# CamLink.net
KiCad netlist of a schematic drawn in Altium Designer
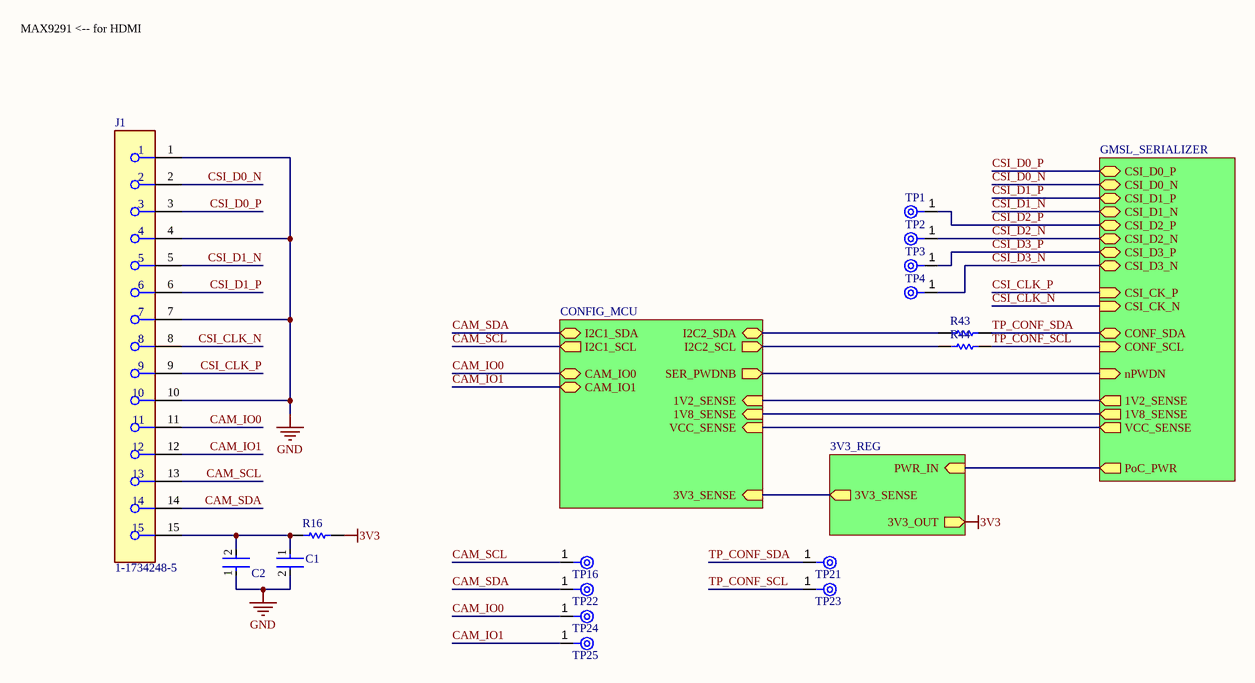
[diagram p0: CamLink.SchDoc]

(export (version "E")
  (design (tool "Eeschema 10.0.6"))
  (components
    (comp (ref "C1")
      (value "CL05A106MP5NUNC")
      (footprint "FP-CL05A106MP5NUNC-MFG")
      (description "CAP CER 10UF 10V X5R 0402")
      (fields
        (field (name "OCTOPART") "https://octopart.com/cl05a106mp5nunc-samsung-22457395")
        (field (name "TOLERANCE") "20%")
      )
      (libsource (lib "Altium Content Vault") (part "b4654b650e69147ec39a6b967a45e02"))
    )
    (comp (ref "C2")
      (value "C1005X7R1H104K050BB")
      (footprint "FP-C1005-050-0_05-IPC_C")
      (description "Multilayer Ceramic Capacitors 100nF ±10% 50V X7R SMD 0402")
      (fields (field (name "VOLTAGE") "50V") (field (name "TOLERANCE") "10%"))
      (libsource (lib "Altium Content Vault") (part "b4654b650e69147ec39a6b967a45e02"))
    )
    (comp (ref "J1")
      (value "1-1734248-5")
      (footprint "FP-1-1734248-5-MFG")
      (description "CONN FPC VERT 15POS 1.00MM SMD")
      (fields
        (field (name "MANUFACTURER") "TE")
        (field (name "OCTOPART") "https://octopart.com/1-1734248-5-te+connectivity-40620898")
      )
      (libsource (lib "Altium Content Vault") (part "a0777be16b290adccad2a8f9338c195"))
    )
    (comp (ref "R16")
      (value "RC0402JR-070RL")
      (footprint "RESC1005X40X25NL05T10")
      (fields (field (name "MANUFACTURER") "Yageo / Phycomp"))
      (libsource (lib "Altium Content Vault") (part "RES"))
    )
    (comp (ref "R43")
      (value "RC0402JR-070RL")
      (footprint "RESC1005X40X25NL05T10")
      (fields (field (name "MANUFACTURER") "Yageo / Phycomp"))
      (libsource (lib "Altium Content Vault") (part "RES"))
    )
    (comp (ref "R44")
      (value "RC0402JR-070RL")
      (footprint "RESC1005X40X25NL05T10")
      (fields (field (name "MANUFACTURER") "Yageo / Phycomp"))
      (libsource (lib "Altium Content Vault") (part "RES"))
    )
    (comp (ref "TP1")
      (value "TPAD6R")
      (footprint "New footprint 1")
      (description "Test Point .6mm")
      (libsource (lib "Space Concordia") (part "TP"))
    )
    (comp (ref "TP2")
      (value "TPAD6R")
      (footprint "New footprint 1")
      (description "Test Point .6mm")
      (libsource (lib "Space Concordia") (part "TP"))
    )
    (comp (ref "TP3")
      (value "TPAD6R")
      (footprint "New footprint 1")
      (description "Test Point .6mm")
      (libsource (lib "Space Concordia") (part "TP"))
    )
    (comp (ref "TP4")
      (value "TPAD6R")
      (footprint "New footprint 1")
      (description "Test Point .6mm")
      (libsource (lib "Space Concordia") (part "TP"))
    )
    (comp (ref "TP16")
      (value "TPAD6R")
      (footprint "New footprint 1")
      (description "Test Point .6mm")
      (libsource (lib "Space Concordia") (part "TP"))
    )
    (comp (ref "TP21")
      (value "TPAD6R")
      (footprint "New footprint 1")
      (description "Test Point .6mm")
      (libsource (lib "Space Concordia") (part "TP"))
    )
    (comp (ref "TP22")
      (value "TPAD6R")
      (footprint "New footprint 1")
      (description "Test Point .6mm")
      (libsource (lib "Space Concordia") (part "TP"))
    )
    (comp (ref "TP23")
      (value "TPAD6R")
      (footprint "New footprint 1")
      (description "Test Point .6mm")
      (libsource (lib "Space Concordia") (part "TP"))
    )
    (comp (ref "TP24")
      (value "TPAD6R")
      (footprint "New footprint 1")
      (description "Test Point .6mm")
      (libsource (lib "Space Concordia") (part "TP"))
    )
    (comp (ref "TP25")
      (value "TPAD6R")
      (footprint "New footprint 1")
      (description "Test Point .6mm")
      (libsource (lib "Space Concordia") (part "TP"))
    )
  )
  (nets
    (net (code "4") (name "/CAM_IO0") (class "Default")
      (node (ref "J1") (pin "11") (pinfunction "11_11") (pintype "passive"))
      (node (ref "TP24") (pin "1") (pinfunction "TP_1") (pintype "passive"))
    )
    (net (code "5") (name "/CAM_IO1") (class "Default")
      (node (ref "J1") (pin "12") (pinfunction "12_12") (pintype "passive"))
      (node (ref "TP25") (pin "1") (pinfunction "TP_1") (pintype "passive"))
    )
    (net (code "6") (name "/CAM_SCL") (class "Default")
      (node (ref "J1") (pin "13") (pinfunction "13_13") (pintype "passive"))
      (node (ref "TP16") (pin "1") (pinfunction "TP_1") (pintype "passive"))
    )
    (net (code "7") (name "/CAM_SDA") (class "Default")
      (node (ref "J1") (pin "14") (pinfunction "14_14") (pintype "passive"))
      (node (ref "TP22") (pin "1") (pinfunction "TP_1") (pintype "passive"))
    )
    (net (code "8") (name "/CSI_CLK_N") (class "Default")
      (node (ref "J1") (pin "8") (pinfunction "8_8") (pintype "passive"))
    )
    (net (code "9") (name "/CSI_CLK_P") (class "Default")
      (node (ref "J1") (pin "9") (pinfunction "9_9") (pintype "passive"))
    )
    (net (code "10") (name "/CSI_D0_N") (class "Default")
      (node (ref "J1") (pin "2") (pinfunction "2_2") (pintype "passive"))
    )
    (net (code "11") (name "/CSI_D0_P") (class "Default")
      (node (ref "J1") (pin "3") (pinfunction "3_3") (pintype "passive"))
    )
    (net (code "12") (name "/CSI_D1_N") (class "Default")
      (node (ref "J1") (pin "5") (pinfunction "5_5") (pintype "passive"))
    )
    (net (code "13") (name "/CSI_D1_P") (class "Default")
      (node (ref "J1") (pin "6") (pinfunction "6_6") (pintype "passive"))
    )
    (net (code "14") (name "/CSI_D2_N") (class "Default")
      (node (ref "TP2") (pin "1") (pinfunction "TP_1") (pintype "passive"))
    )
    (net (code "15") (name "/CSI_D2_P") (class "Default")
      (node (ref "TP1") (pin "1") (pinfunction "TP_1") (pintype "passive"))
    )
    (net (code "16") (name "/CSI_D3_N") (class "Default")
      (node (ref "TP4") (pin "1") (pinfunction "TP_1") (pintype "passive"))
    )
    (net (code "17") (name "/CSI_D3_P") (class "Default")
      (node (ref "TP3") (pin "1") (pinfunction "TP_1") (pintype "passive"))
    )
    (net (code "18") (name "/I2C2_SCL") (class "Default")
      (node (ref "R44") (pin "1") (pinfunction "1_1") (pintype "passive"))
    )
    (net (code "19") (name "/I2C2_SDA") (class "Default")
      (node (ref "R43") (pin "1") (pinfunction "1_1") (pintype "passive"))
    )
    (net (code "22") (name "/TP_CONF_SCL") (class "Default")
      (node (ref "R44") (pin "2") (pinfunction "2_2") (pintype "passive"))
      (node (ref "TP23") (pin "1") (pinfunction "TP_1") (pintype "passive"))
    )
    (net (code "23") (name "/TP_CONF_SDA") (class "Default")
      (node (ref "R43") (pin "2") (pinfunction "2_2") (pintype "passive"))
      (node (ref "TP21") (pin "1") (pinfunction "TP_1") (pintype "passive"))
    )
    (net (code "25") (name "3V3") (class "Default")
      (node (ref "R16") (pin "2") (pinfunction "2_2") (pintype "passive"))
    )
    (net (code "26") (name "GND") (class "Default")
      (node (ref "C1") (pin "2") (pinfunction "2_2") (pintype "passive"))
      (node (ref "C2") (pin "1") (pinfunction "1_1") (pintype "passive"))
      (node (ref "J1") (pin "1") (pinfunction "1_1") (pintype "passive"))
      (node (ref "J1") (pin "10") (pinfunction "10_10") (pintype "passive"))
      (node (ref "J1") (pin "4") (pinfunction "4_4") (pintype "passive"))
      (node (ref "J1") (pin "7") (pinfunction "7_7") (pintype "passive"))
    )
    (net (code "27") (name "Net-(C1-Pad1)") (class "Default")
      (node (ref "C1") (pin "1") (pinfunction "1_1") (pintype "passive"))
      (node (ref "C2") (pin "2") (pinfunction "2_2") (pintype "passive"))
      (node (ref "J1") (pin "15") (pinfunction "15_15") (pintype "passive"))
      (node (ref "R16") (pin "1") (pinfunction "1_1") (pintype "passive"))
    )
  )
)
